# LSS.net
KiCad netlist of a schematic drawn in EAGLE
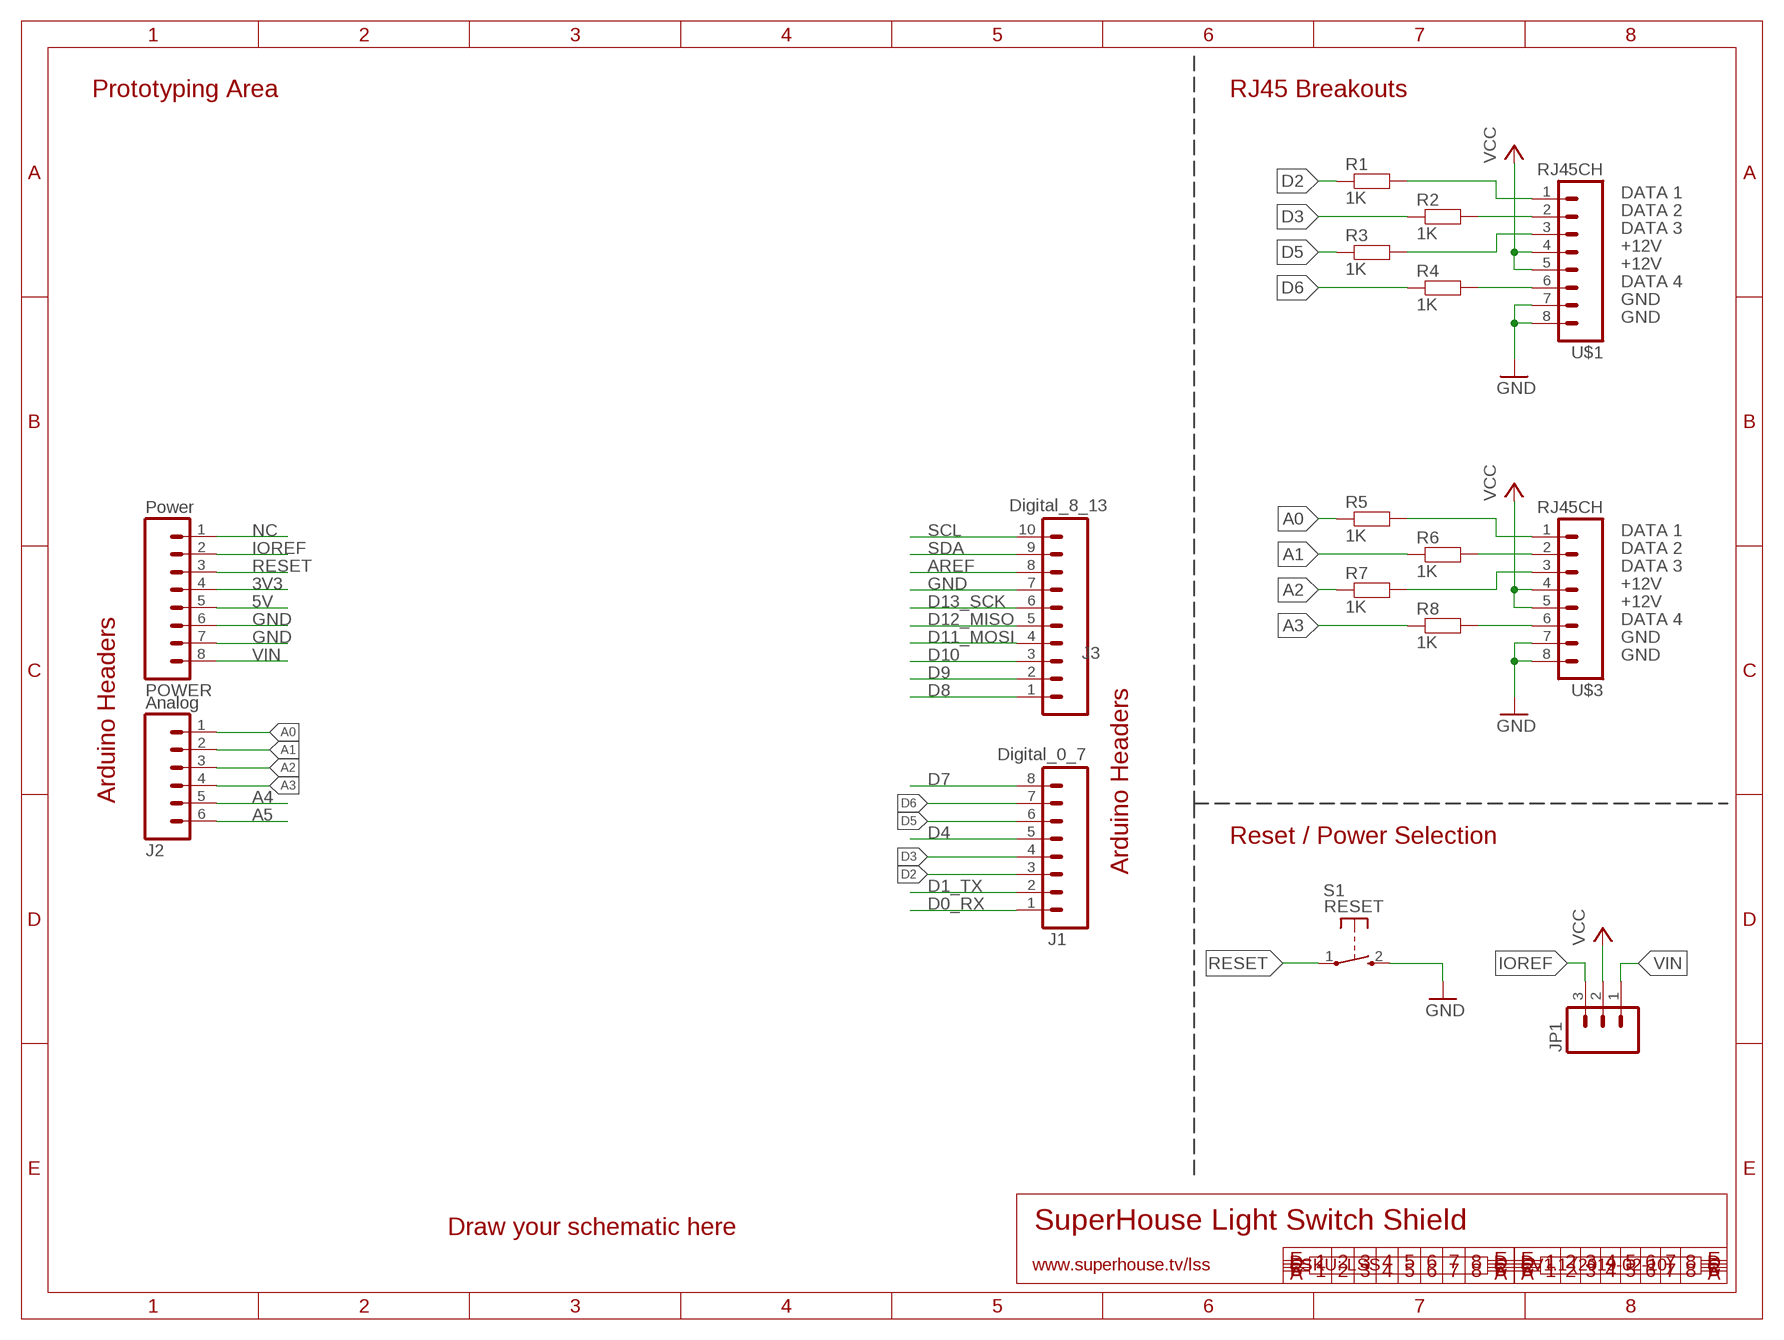
[diagram p0: schematic, sheet 1]

(export (version "E")
  (design (tool "Eeschema 10.0.6"))
  (components
    (comp (ref "J1")
      (value "Digital_0_7")
      (footprint "eagle-import:1X08")
      (libsource (lib "eagle-import") (part "M08"))
    )
    (comp (ref "J2")
      (value "Analog")
      (footprint "eagle-import:1X06")
      (libsource (lib "eagle-import") (part "M06SIP"))
    )
    (comp (ref "J3")
      (value "Digital_8_13")
      (footprint "eagle-import:1X10")
      (libsource (lib "eagle-import") (part "M100.1"))
    )
    (comp (ref "JP1")
      (value "M03PTH")
      (footprint "eagle-import:1X03")
      (libsource (lib "eagle-import") (part "M03PTH"))
    )
    (comp (ref "POWER")
      (value "Power")
      (footprint "eagle-import:1X08")
      (libsource (lib "eagle-import") (part "freetronics-original_M08"))
    )
    (comp (ref "R1")
      (value "1K")
      (footprint "eagle-import:0603")
      (libsource (lib "eagle-import") (part "RESISTOR0603"))
    )
    (comp (ref "R2")
      (value "1K")
      (footprint "eagle-import:0603")
      (libsource (lib "eagle-import") (part "RESISTOR0603"))
    )
    (comp (ref "R3")
      (value "1K")
      (footprint "eagle-import:0603")
      (libsource (lib "eagle-import") (part "RESISTOR0603"))
    )
    (comp (ref "R4")
      (value "1K")
      (footprint "eagle-import:0603")
      (libsource (lib "eagle-import") (part "RESISTOR0603"))
    )
    (comp (ref "R5")
      (value "1K")
      (footprint "eagle-import:0603")
      (libsource (lib "eagle-import") (part "RESISTOR0603"))
    )
    (comp (ref "R6")
      (value "1K")
      (footprint "eagle-import:0603")
      (libsource (lib "eagle-import") (part "RESISTOR0603"))
    )
    (comp (ref "R7")
      (value "1K")
      (footprint "eagle-import:0603")
      (libsource (lib "eagle-import") (part "RESISTOR0603"))
    )
    (comp (ref "R8")
      (value "1K")
      (footprint "eagle-import:0603")
      (libsource (lib "eagle-import") (part "RESISTOR0603"))
    )
    (comp (ref "S1")
      (value "RESET")
      (footprint "eagle-import:TACTILE_SWITCH_SMD_2PIN_TINY")
      (libsource (lib "eagle-import") (part "TAC_SWITCH_2PINSMT"))
    )
    (comp (ref "U$1")
      (value "RJ45CH")
      (footprint "eagle-import:RJ45CH")
      (libsource (lib "eagle-import") (part "RJ45CH"))
    )
    (comp (ref "U$3")
      (value "RJ45CH")
      (footprint "eagle-import:RJ45CH")
      (libsource (lib "eagle-import") (part "RJ45CH"))
    )
  )
  (nets
    (net (code "1") (name "/3V3") (class "Default")
      (node (ref "POWER") (pin "4") (pinfunction "4_4") (pintype "passive"))
    )
    (net (code "2") (name "/5V") (class "Default")
      (node (ref "POWER") (pin "5") (pinfunction "5_5") (pintype "passive"))
    )
    (net (code "3") (name "/A4") (class "Default")
      (node (ref "J2") (pin "5") (pinfunction "5_5") (pintype "passive"))
    )
    (net (code "4") (name "/A5") (class "Default")
      (node (ref "J2") (pin "6") (pinfunction "6_6") (pintype "passive"))
    )
    (net (code "5") (name "/AREF") (class "Default")
      (node (ref "J3") (pin "8") (pinfunction "8_8") (pintype "passive"))
    )
    (net (code "6") (name "/D0_RX") (class "Default")
      (node (ref "J1") (pin "1") (pinfunction "1_1") (pintype "passive"))
    )
    (net (code "7") (name "/D1_TX") (class "Default")
      (node (ref "J1") (pin "2") (pinfunction "2_2") (pintype "passive"))
    )
    (net (code "8") (name "/D4") (class "Default")
      (node (ref "J1") (pin "5") (pinfunction "5_5") (pintype "passive"))
    )
    (net (code "9") (name "/D7") (class "Default")
      (node (ref "J1") (pin "8") (pinfunction "8_8") (pintype "passive"))
    )
    (net (code "10") (name "/D8") (class "Default")
      (node (ref "J3") (pin "1") (pinfunction "1_1") (pintype "passive"))
    )
    (net (code "11") (name "/D9") (class "Default")
      (node (ref "J3") (pin "2") (pinfunction "2_2") (pintype "passive"))
    )
    (net (code "12") (name "/D10") (class "Default")
      (node (ref "J3") (pin "3") (pinfunction "3_3") (pintype "passive"))
    )
    (net (code "13") (name "/D11_MOSI") (class "Default")
      (node (ref "J3") (pin "4") (pinfunction "4_4") (pintype "passive"))
    )
    (net (code "14") (name "/D12_MISO") (class "Default")
      (node (ref "J3") (pin "5") (pinfunction "5_5") (pintype "passive"))
    )
    (net (code "15") (name "/D13_SCK") (class "Default")
      (node (ref "J3") (pin "6") (pinfunction "6_6") (pintype "passive"))
    )
    (net (code "16") (name "/NC") (class "Default")
      (node (ref "POWER") (pin "1") (pinfunction "1_1") (pintype "passive"))
    )
    (net (code "17") (name "/SCL") (class "Default")
      (node (ref "J3") (pin "10") (pinfunction "10_10") (pintype "passive"))
    )
    (net (code "18") (name "/SDA") (class "Default")
      (node (ref "J3") (pin "9") (pinfunction "9_9") (pintype "passive"))
    )
    (net (code "19") (name "A0") (class "Default")
      (node (ref "J2") (pin "1") (pinfunction "1_1") (pintype "passive"))
      (node (ref "R5") (pin "1") (pinfunction "1_1") (pintype "passive"))
    )
    (net (code "20") (name "A1") (class "Default")
      (node (ref "J2") (pin "2") (pinfunction "2_2") (pintype "passive"))
      (node (ref "R6") (pin "1") (pinfunction "1_1") (pintype "passive"))
    )
    (net (code "21") (name "A2") (class "Default")
      (node (ref "J2") (pin "3") (pinfunction "3_3") (pintype "passive"))
      (node (ref "R7") (pin "1") (pinfunction "1_1") (pintype "passive"))
    )
    (net (code "22") (name "A3") (class "Default")
      (node (ref "J2") (pin "4") (pinfunction "4_4") (pintype "passive"))
      (node (ref "R8") (pin "1") (pinfunction "1_1") (pintype "passive"))
    )
    (net (code "23") (name "D2") (class "Default")
      (node (ref "J1") (pin "3") (pinfunction "3_3") (pintype "passive"))
      (node (ref "R1") (pin "1") (pinfunction "1_1") (pintype "passive"))
    )
    (net (code "24") (name "D3") (class "Default")
      (node (ref "J1") (pin "4") (pinfunction "4_4") (pintype "passive"))
      (node (ref "R2") (pin "1") (pinfunction "1_1") (pintype "passive"))
    )
    (net (code "25") (name "D5") (class "Default")
      (node (ref "J1") (pin "6") (pinfunction "6_6") (pintype "passive"))
      (node (ref "R3") (pin "1") (pinfunction "1_1") (pintype "passive"))
    )
    (net (code "26") (name "D6") (class "Default")
      (node (ref "J1") (pin "7") (pinfunction "7_7") (pintype "passive"))
      (node (ref "R4") (pin "1") (pinfunction "1_1") (pintype "passive"))
    )
    (net (code "27") (name "GND") (class "Default")
      (node (ref "J3") (pin "7") (pinfunction "7_7") (pintype "passive"))
      (node (ref "POWER") (pin "6") (pinfunction "6_6") (pintype "passive"))
      (node (ref "POWER") (pin "7") (pinfunction "7_7") (pintype "passive"))
      (node (ref "S1") (pin "2") (pinfunction "S_2") (pintype "passive"))
      (node (ref "U$1") (pin "7") (pinfunction "7_7") (pintype "passive"))
      (node (ref "U$1") (pin "8") (pinfunction "8_8") (pintype "passive"))
      (node (ref "U$3") (pin "7") (pinfunction "7_7") (pintype "passive"))
      (node (ref "U$3") (pin "8") (pinfunction "8_8") (pintype "passive"))
    )
    (net (code "28") (name "IOREF") (class "Default")
      (node (ref "JP1") (pin "3") (pinfunction "3_3") (pintype "passive"))
      (node (ref "POWER") (pin "2") (pinfunction "2_2") (pintype "passive"))
    )
    (net (code "29") (name "Net-(R1-Pad2)") (class "Default")
      (node (ref "R1") (pin "2") (pinfunction "2_2") (pintype "passive"))
      (node (ref "U$1") (pin "1") (pinfunction "1_1") (pintype "passive"))
    )
    (net (code "30") (name "Net-(R2-Pad2)") (class "Default")
      (node (ref "R2") (pin "2") (pinfunction "2_2") (pintype "passive"))
      (node (ref "U$1") (pin "2") (pinfunction "2_2") (pintype "passive"))
    )
    (net (code "31") (name "Net-(R3-Pad2)") (class "Default")
      (node (ref "R3") (pin "2") (pinfunction "2_2") (pintype "passive"))
      (node (ref "U$1") (pin "3") (pinfunction "3_3") (pintype "passive"))
    )
    (net (code "32") (name "Net-(R4-Pad2)") (class "Default")
      (node (ref "R4") (pin "2") (pinfunction "2_2") (pintype "passive"))
      (node (ref "U$1") (pin "6") (pinfunction "6_6") (pintype "passive"))
    )
    (net (code "33") (name "Net-(R5-Pad2)") (class "Default")
      (node (ref "R5") (pin "2") (pinfunction "2_2") (pintype "passive"))
      (node (ref "U$3") (pin "1") (pinfunction "1_1") (pintype "passive"))
    )
    (net (code "34") (name "Net-(R6-Pad2)") (class "Default")
      (node (ref "R6") (pin "2") (pinfunction "2_2") (pintype "passive"))
      (node (ref "U$3") (pin "2") (pinfunction "2_2") (pintype "passive"))
    )
    (net (code "35") (name "Net-(R7-Pad2)") (class "Default")
      (node (ref "R7") (pin "2") (pinfunction "2_2") (pintype "passive"))
      (node (ref "U$3") (pin "3") (pinfunction "3_3") (pintype "passive"))
    )
    (net (code "36") (name "Net-(R8-Pad2)") (class "Default")
      (node (ref "R8") (pin "2") (pinfunction "2_2") (pintype "passive"))
      (node (ref "U$3") (pin "6") (pinfunction "6_6") (pintype "passive"))
    )
    (net (code "37") (name "RESET") (class "Default")
      (node (ref "POWER") (pin "3") (pinfunction "3_3") (pintype "passive"))
      (node (ref "S1") (pin "1") (pinfunction "P_1") (pintype "passive"))
    )
    (net (code "38") (name "VCC") (class "Default")
      (node (ref "JP1") (pin "2") (pinfunction "2_2") (pintype "passive"))
      (node (ref "U$1") (pin "4") (pinfunction "4_4") (pintype "passive"))
      (node (ref "U$1") (pin "5") (pinfunction "5_5") (pintype "passive"))
      (node (ref "U$3") (pin "4") (pinfunction "4_4") (pintype "passive"))
      (node (ref "U$3") (pin "5") (pinfunction "5_5") (pintype "passive"))
    )
    (net (code "39") (name "VIN") (class "Default")
      (node (ref "JP1") (pin "1") (pinfunction "1_1") (pintype "passive"))
      (node (ref "POWER") (pin "8") (pinfunction "8_8") (pintype "passive"))
    )
  )
)
